# Beacon_schematic.net
KiCad netlist of a schematic drawn in EAGLE
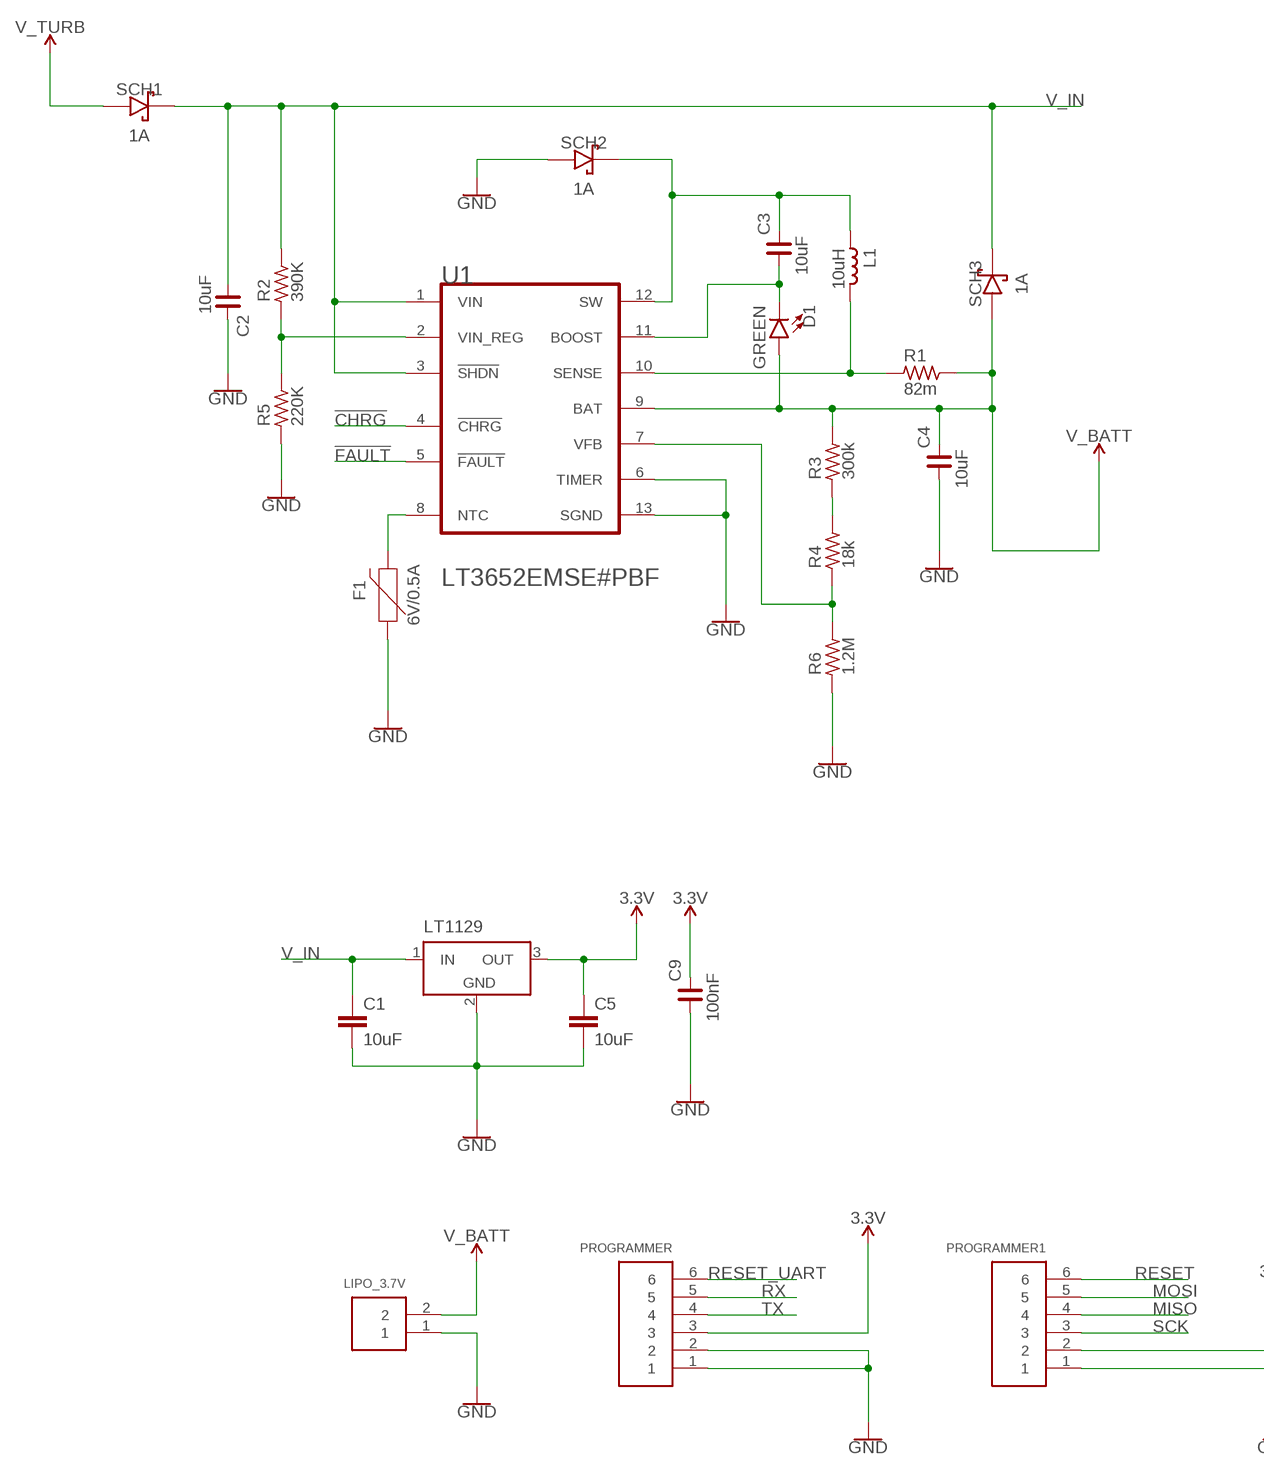
[diagram p0: schematic, sheet 1, part 1 of 2]
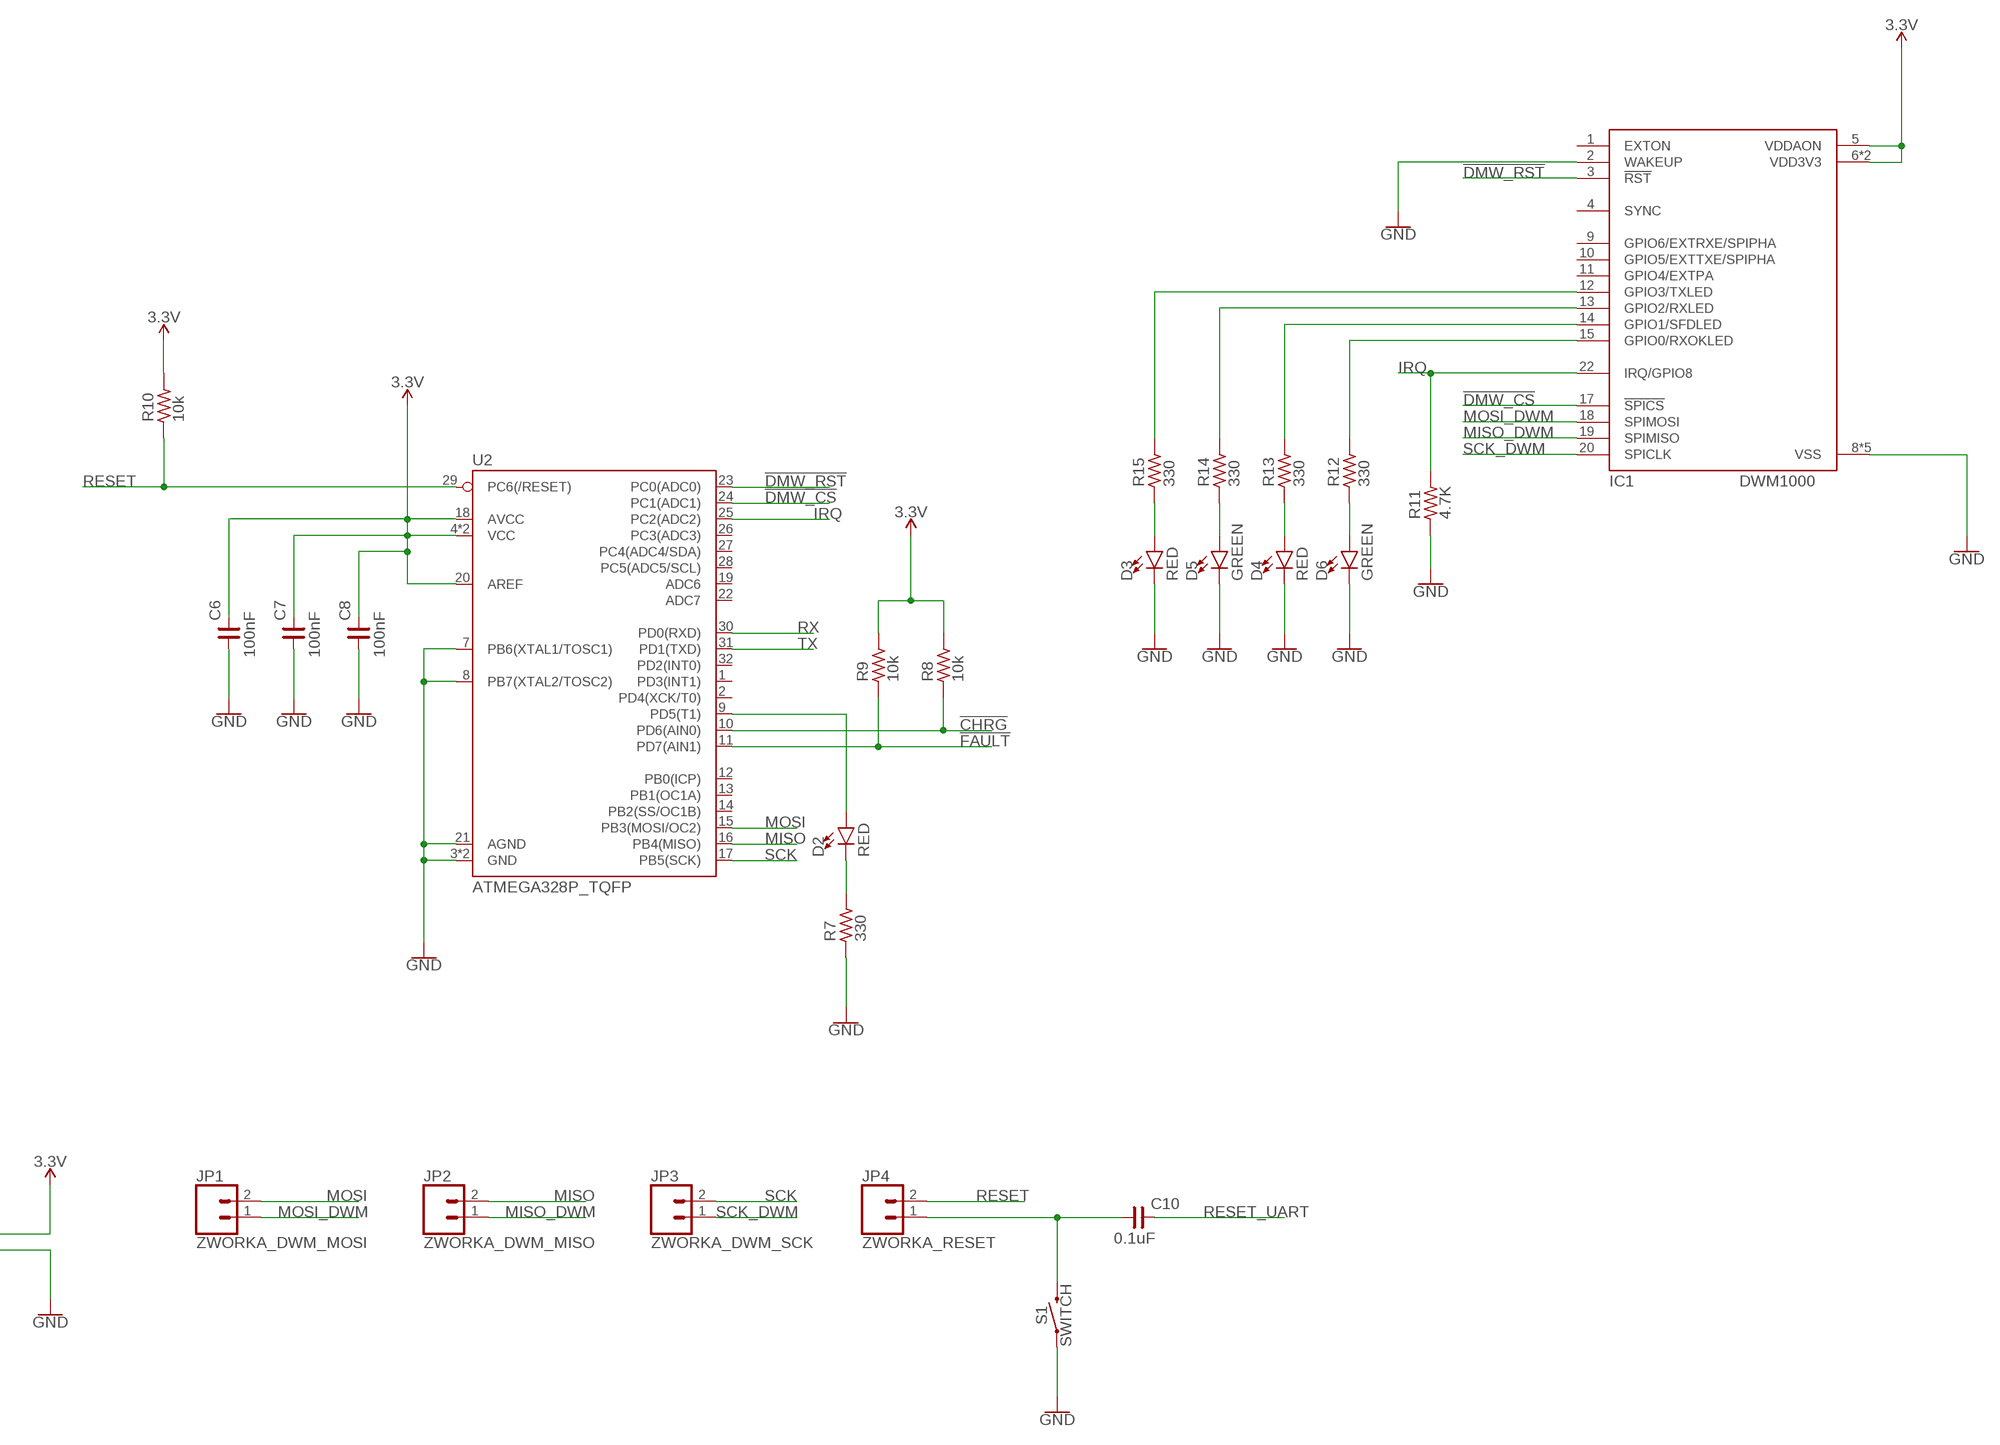
[diagram p1: schematic, sheet 1, part 2 of 2]

(export (version "E")
  (design (tool "Eeschema 10.0.6"))
  (components
    (comp (ref "C1")
      (value "10uF")
      (footprint "eagle-import:1206")
      (libsource (lib "eagle-import") (part "10UF-1206-6.3V-20%"))
    )
    (comp (ref "C2")
      (value "10uF")
      (footprint "eagle-import:C1206")
      (libsource (lib "eagle-import") (part "C_1206"))
    )
    (comp (ref "C3")
      (value "10uF")
      (footprint "eagle-import:C1206")
      (libsource (lib "eagle-import") (part "C_1206"))
    )
    (comp (ref "C4")
      (value "10uF")
      (footprint "eagle-import:C1206")
      (libsource (lib "eagle-import") (part "C_1206"))
    )
    (comp (ref "C5")
      (value "10uF")
      (footprint "eagle-import:1206")
      (libsource (lib "eagle-import") (part "10UF-1206-6.3V-20%"))
    )
    (comp (ref "C6")
      (value "100nF")
      (footprint "eagle-import:C1206")
      (libsource (lib "eagle-import") (part "C_1206"))
    )
    (comp (ref "C7")
      (value "100nF")
      (footprint "eagle-import:C1206")
      (libsource (lib "eagle-import") (part "C_1206"))
    )
    (comp (ref "C8")
      (value "100nF")
      (footprint "eagle-import:C1206")
      (libsource (lib "eagle-import") (part "C_1206"))
    )
    (comp (ref "C9")
      (value "100nF")
      (footprint "eagle-import:C1206")
      (libsource (lib "eagle-import") (part "C_1206"))
    )
    (comp (ref "C10")
      (value "0.1uF")
      (footprint "eagle-import:C1206")
      (libsource (lib "eagle-import") (part "C_1206"))
    )
    (comp (ref "D1")
      (value "GREEN")
      (footprint "eagle-import:LED-1206")
      (libsource (lib "eagle-import") (part "LED-GREEN1206"))
    )
    (comp (ref "D2")
      (value "RED")
      (footprint "eagle-import:LED-1206")
      (libsource (lib "eagle-import") (part "LED-RED1206"))
    )
    (comp (ref "D3")
      (value "RED")
      (footprint "eagle-import:LED-1206")
      (libsource (lib "eagle-import") (part "LED-RED1206"))
    )
    (comp (ref "D4")
      (value "RED")
      (footprint "eagle-import:LED-1206")
      (libsource (lib "eagle-import") (part "LED-RED1206"))
    )
    (comp (ref "D5")
      (value "GREEN")
      (footprint "eagle-import:LED-1206")
      (libsource (lib "eagle-import") (part "LED-GREENLILYPAD"))
    )
    (comp (ref "D6")
      (value "GREEN")
      (footprint "eagle-import:LED-1206")
      (libsource (lib "eagle-import") (part "LED-GREENLILYPAD"))
    )
    (comp (ref "F1")
      (value "6V/0.5A")
      (footprint "eagle-import:1206")
      (libsource (lib "eagle-import") (part "PPTC_HALF-AMP"))
    )
    (comp (ref "IC1")
      (value "DWM1000")
      (footprint "eagle-import:DWM1000")
      (libsource (lib "eagle-import") (part "DWM1000"))
    )
    (comp (ref "JP1")
      (value "ZWORKA_DWM_MOSI")
      (footprint "eagle-import:1X02")
      (libsource (lib "eagle-import") (part "CONN_02"))
    )
    (comp (ref "JP2")
      (value "ZWORKA_DWM_MISO")
      (footprint "eagle-import:1X02")
      (libsource (lib "eagle-import") (part "CONN_02"))
    )
    (comp (ref "JP3")
      (value "ZWORKA_DWM_SCK")
      (footprint "eagle-import:1X02")
      (libsource (lib "eagle-import") (part "CONN_02"))
    )
    (comp (ref "JP4")
      (value "ZWORKA_RESET")
      (footprint "eagle-import:1X02")
      (libsource (lib "eagle-import") (part "CONN_02"))
    )
    (comp (ref "L1")
      (value "10uH")
      (footprint "eagle-import:L1206")
      (libsource (lib "eagle-import") (part "L_1206"))
    )
    (comp (ref "LIPO_3.7V")
      (value "2PIN")
      (footprint "eagle-import:B2B-PH-K-S")
      (libsource (lib "eagle-import") (part "2PIN"))
    )
    (comp (ref "LT1129")
      (value "LT1129CST5")
      (footprint "eagle-import:SOT223")
      (libsource (lib "eagle-import") (part "LT1129CST5"))
    )
    (comp (ref "PROGRAMMER")
      (value "6PIN")
      (footprint "eagle-import:B6B-PH-K-S")
      (libsource (lib "eagle-import") (part "6PIN"))
    )
    (comp (ref "PROGRAMMER1")
      (value "6PIN")
      (footprint "eagle-import:B6B-PH-K-S")
      (libsource (lib "eagle-import") (part "6PIN"))
    )
    (comp (ref "R1")
      (value "82m")
      (footprint "eagle-import:R1206")
      (libsource (lib "eagle-import") (part "R_1206"))
    )
    (comp (ref "R2")
      (value "390K")
      (footprint "eagle-import:R1206")
      (libsource (lib "eagle-import") (part "R_1206"))
    )
    (comp (ref "R3")
      (value "300k")
      (footprint "eagle-import:R1206")
      (libsource (lib "eagle-import") (part "R_1206"))
    )
    (comp (ref "R4")
      (value "18k")
      (footprint "eagle-import:R1206")
      (libsource (lib "eagle-import") (part "R_1206"))
    )
    (comp (ref "R5")
      (value "220K")
      (footprint "eagle-import:R1206")
      (libsource (lib "eagle-import") (part "R_1206"))
    )
    (comp (ref "R6")
      (value "1.2M")
      (footprint "eagle-import:R1206")
      (libsource (lib "eagle-import") (part "R_1206"))
    )
    (comp (ref "R7")
      (value "330")
      (footprint "eagle-import:R1206")
      (libsource (lib "eagle-import") (part "R_1206"))
    )
    (comp (ref "R8")
      (value "10k")
      (footprint "eagle-import:R1206")
      (libsource (lib "eagle-import") (part "R_1206"))
    )
    (comp (ref "R9")
      (value "10k")
      (footprint "eagle-import:R1206")
      (libsource (lib "eagle-import") (part "R_1206"))
    )
    (comp (ref "R10")
      (value "10k")
      (footprint "eagle-import:R1206")
      (libsource (lib "eagle-import") (part "R_1206"))
    )
    (comp (ref "R11")
      (value "4.7K")
      (footprint "eagle-import:R1206")
      (libsource (lib "eagle-import") (part "R_1206"))
    )
    (comp (ref "R12")
      (value "330")
      (footprint "eagle-import:R1206")
      (libsource (lib "eagle-import") (part "R_1206"))
    )
    (comp (ref "R13")
      (value "330")
      (footprint "eagle-import:R1206")
      (libsource (lib "eagle-import") (part "R_1206"))
    )
    (comp (ref "R14")
      (value "330")
      (footprint "eagle-import:R1206")
      (libsource (lib "eagle-import") (part "R_1206"))
    )
    (comp (ref "R15")
      (value "330")
      (footprint "eagle-import:R1206")
      (libsource (lib "eagle-import") (part "R_1206"))
    )
    (comp (ref "S1")
      (value "SWITCH")
      (footprint "eagle-import:TACTILE_SWITCH_SMD_5.2MM")
      (libsource (lib "eagle-import") (part "MOMENTARY-SWITCH-SPST-SMD-5.2-REDUNDANT"))
    )
    (comp (ref "SCH1")
      (value "1A")
      (footprint "eagle-import:SOD123")
      (fields (field (name "MANUFACTURER") "ON Semiconductor") (field (name "MPN") "MBR0520LT1G"))
      (libsource (lib "eagle-import") (part "DIODE_SCHOTTKYMBR0520LT1G"))
    )
    (comp (ref "SCH2")
      (value "1A")
      (footprint "eagle-import:SOD123")
      (fields (field (name "MANUFACTURER") "ON Semiconductor") (field (name "MPN") "MBR0520LT1G"))
      (libsource (lib "eagle-import") (part "DIODE_SCHOTTKYMBR0520LT1G"))
    )
    (comp (ref "SCH3")
      (value "1A")
      (footprint "eagle-import:SOD123")
      (fields (field (name "MANUFACTURER") "ON Semiconductor") (field (name "MPN") "MBR0520LT1G"))
      (libsource (lib "eagle-import") (part "DIODE_SCHOTTKYMBR0520LT1G"))
    )
    (comp (ref "U1")
      (value "LINEAR_TECHNOLOGY_LT3652EMSE#PBFLINEAR_TECHNOLOGY_LT3652EMSE#PBF_0_2")
      (footprint "eagle-import:LINEAR_TECHNOLOGY_LT3652EMSE#PBF_2")
      (fields (field (name "MF") "Linear Technology") (field (name "MPN") "LT3652EMSE#PBF"))
      (libsource (lib "eagle-import") (part "LINEAR_TECHNOLOGY_LT3652EMSE#PBFLINEAR_TECHNOLOGY_LT3652EMSE#PBF_0_2"))
    )
    (comp (ref "U2")
      (value "ATMEGA328P_TQFP")
      (footprint "eagle-import:TQFP32-08")
      (libsource (lib "eagle-import") (part "ATMEGA328P_TQFP"))
    )
  )
  (nets
    (net (code "1") (name "/IRQ") (class "Default")
      (node (ref "IC1") (pin "22") (pinfunction "IRQ/GPIO8_22") (pintype "bidirectional"))
      (node (ref "R11") (pin "2") (pinfunction "2_2") (pintype "passive"))
      (node (ref "U2") (pin "25") (pinfunction "PC2(ADC2)_25") (pintype "bidirectional"))
    )
    (net (code "2") (name "/MISO") (class "Default")
      (node (ref "JP2") (pin "2") (pinfunction "2_2") (pintype "passive"))
      (node (ref "PROGRAMMER1") (pin "4") (pinfunction "4_4") (pintype "bidirectional"))
      (node (ref "U2") (pin "16") (pinfunction "PB4(MISO)_16") (pintype "bidirectional"))
    )
    (net (code "3") (name "/MISO_DWM") (class "Default")
      (node (ref "IC1") (pin "19") (pinfunction "SPIMISO_19") (pintype "bidirectional"))
      (node (ref "JP2") (pin "1") (pinfunction "1_1") (pintype "passive"))
    )
    (net (code "4") (name "/MOSI") (class "Default")
      (node (ref "JP1") (pin "2") (pinfunction "2_2") (pintype "passive"))
      (node (ref "PROGRAMMER1") (pin "5") (pinfunction "5_5") (pintype "bidirectional"))
      (node (ref "U2") (pin "15") (pinfunction "PB3(MOSI/OC2)_15") (pintype "bidirectional"))
    )
    (net (code "5") (name "/MOSI_DWM") (class "Default")
      (node (ref "IC1") (pin "18") (pinfunction "SPIMOSI_18") (pintype "bidirectional"))
      (node (ref "JP1") (pin "1") (pinfunction "1_1") (pintype "passive"))
    )
    (net (code "6") (name "/RESET") (class "Default")
      (node (ref "JP4") (pin "2") (pinfunction "2_2") (pintype "passive"))
      (node (ref "PROGRAMMER1") (pin "6") (pinfunction "6_6") (pintype "bidirectional"))
      (node (ref "R10") (pin "1") (pinfunction "1_1") (pintype "passive"))
      (node (ref "U2") (pin "29") (pinfunction "PC6(/RESET)_29") (pintype "bidirectional"))
    )
    (net (code "7") (name "/RESET_UART") (class "Default")
      (node (ref "C10") (pin "2") (pinfunction "2_2") (pintype "passive"))
      (node (ref "PROGRAMMER") (pin "6") (pinfunction "6_6") (pintype "bidirectional"))
    )
    (net (code "8") (name "/RX") (class "Default")
      (node (ref "PROGRAMMER") (pin "5") (pinfunction "5_5") (pintype "bidirectional"))
      (node (ref "U2") (pin "30") (pinfunction "PD0(RXD)_30") (pintype "bidirectional"))
    )
    (net (code "9") (name "/SCK") (class "Default")
      (node (ref "JP3") (pin "2") (pinfunction "2_2") (pintype "passive"))
      (node (ref "PROGRAMMER1") (pin "3") (pinfunction "3_3") (pintype "bidirectional"))
      (node (ref "U2") (pin "17") (pinfunction "PB5(SCK)_17") (pintype "bidirectional"))
    )
    (net (code "10") (name "/SCK_DWM") (class "Default")
      (node (ref "IC1") (pin "20") (pinfunction "SPICLK_20") (pintype "bidirectional"))
      (node (ref "JP3") (pin "1") (pinfunction "1_1") (pintype "passive"))
    )
    (net (code "11") (name "/TX") (class "Default")
      (node (ref "PROGRAMMER") (pin "4") (pinfunction "4_4") (pintype "bidirectional"))
      (node (ref "U2") (pin "31") (pinfunction "PD1(TXD)_31") (pintype "bidirectional"))
    )
    (net (code "12") (name "/V_IN") (class "Default")
      (node (ref "C1") (pin "1") (pinfunction "1_1") (pintype "passive"))
      (node (ref "C2") (pin "1") (pinfunction "1_1") (pintype "passive"))
      (node (ref "LT1129") (pin "1") (pinfunction "IN_1") (pintype "input"))
      (node (ref "R2") (pin "2") (pinfunction "2_2") (pintype "passive"))
      (node (ref "SCH1") (pin "K") (pinfunction "CATHODE_K") (pintype "bidirectional"))
      (node (ref "SCH3") (pin "K") (pinfunction "CATHODE_K") (pintype "bidirectional"))
      (node (ref "U1") (pin "1") (pinfunction "VIN_1") (pintype "power_in"))
      (node (ref "U1") (pin "3") (pinfunction "~{SHDN}_3") (pintype "input"))
    )
    (net (code "13") (name "/~{CHRG}") (class "Default")
      (node (ref "R8") (pin "1") (pinfunction "1_1") (pintype "passive"))
      (node (ref "U1") (pin "4") (pinfunction "~{CHRG}_4") (pintype "tri_state"))
      (node (ref "U2") (pin "10") (pinfunction "PD6(AIN0)_10") (pintype "bidirectional"))
    )
    (net (code "14") (name "/~{DMW_CS}") (class "Default")
      (node (ref "IC1") (pin "17") (pinfunction "~{SPICS}_17") (pintype "bidirectional"))
      (node (ref "U2") (pin "24") (pinfunction "PC1(ADC1)_24") (pintype "bidirectional"))
    )
    (net (code "15") (name "/~{DMW_RST}") (class "Default")
      (node (ref "IC1") (pin "3") (pinfunction "~{RST}_3") (pintype "bidirectional"))
      (node (ref "U2") (pin "23") (pinfunction "PC0(ADC0)_23") (pintype "bidirectional"))
    )
    (net (code "16") (name "/~{FAULT}") (class "Default")
      (node (ref "R9") (pin "1") (pinfunction "1_1") (pintype "passive"))
      (node (ref "U1") (pin "5") (pinfunction "~{FAULT}_5") (pintype "tri_state"))
      (node (ref "U2") (pin "11") (pinfunction "PD7(AIN1)_11") (pintype "bidirectional"))
    )
    (net (code "17") (name "3.3V") (class "Default")
      (node (ref "C5") (pin "1") (pinfunction "1_1") (pintype "passive"))
      (node (ref "C6") (pin "2") (pinfunction "2_2") (pintype "passive"))
      (node (ref "C7") (pin "2") (pinfunction "2_2") (pintype "passive"))
      (node (ref "C8") (pin "2") (pinfunction "2_2") (pintype "passive"))
      (node (ref "C9") (pin "2") (pinfunction "2_2") (pintype "passive"))
      (node (ref "IC1") (pin "5") (pinfunction "VDDAON_5") (pintype "bidirectional"))
      (node (ref "IC1") (pin "6") (pinfunction "VDD3V3_6") (pintype "bidirectional"))
      (node (ref "IC1") (pin "7") (pinfunction "VDD3V3_7") (pintype "bidirectional"))
      (node (ref "LT1129") (pin "3") (pinfunction "OUT_3") (pintype "output"))
      (node (ref "PROGRAMMER") (pin "3") (pinfunction "3_3") (pintype "bidirectional"))
      (node (ref "PROGRAMMER1") (pin "2") (pinfunction "2_2") (pintype "bidirectional"))
      (node (ref "R10") (pin "2") (pinfunction "2_2") (pintype "passive"))
      (node (ref "R8") (pin "2") (pinfunction "2_2") (pintype "passive"))
      (node (ref "R9") (pin "2") (pinfunction "2_2") (pintype "passive"))
      (node (ref "U2") (pin "18") (pinfunction "AVCC_18") (pintype "bidirectional"))
      (node (ref "U2") (pin "20") (pinfunction "AREF_20") (pintype "bidirectional"))
      (node (ref "U2") (pin "4") (pinfunction "VCC_4") (pintype "bidirectional"))
      (node (ref "U2") (pin "6") (pinfunction "VCC_6") (pintype "bidirectional"))
    )
    (net (code "18") (name "GND") (class "Default")
      (node (ref "C1") (pin "2") (pinfunction "2_2") (pintype "passive"))
      (node (ref "C2") (pin "2") (pinfunction "2_2") (pintype "passive"))
      (node (ref "C4") (pin "1") (pinfunction "1_1") (pintype "passive"))
      (node (ref "C5") (pin "2") (pinfunction "2_2") (pintype "passive"))
      (node (ref "C6") (pin "1") (pinfunction "1_1") (pintype "passive"))
      (node (ref "C7") (pin "1") (pinfunction "1_1") (pintype "passive"))
      (node (ref "C8") (pin "1") (pinfunction "1_1") (pintype "passive"))
      (node (ref "C9") (pin "1") (pinfunction "1_1") (pintype "passive"))
      (node (ref "D3") (pin "C") (pinfunction "C_C") (pintype "passive"))
      (node (ref "D4") (pin "C") (pinfunction "C_C") (pintype "passive"))
      (node (ref "D5") (pin "C") (pinfunction "C_C") (pintype "passive"))
      (node (ref "D6") (pin "C") (pinfunction "C_C") (pintype "passive"))
      (node (ref "F1") (pin "1") (pinfunction "1_1") (pintype "bidirectional"))
      (node (ref "IC1") (pin "16") (pinfunction "VSS_16") (pintype "bidirectional"))
      (node (ref "IC1") (pin "2") (pinfunction "WAKEUP_2") (pintype "bidirectional"))
      (node (ref "IC1") (pin "21") (pinfunction "VSS_21") (pintype "bidirectional"))
      (node (ref "IC1") (pin "23") (pinfunction "VSS_23") (pintype "bidirectional"))
      (node (ref "IC1") (pin "24") (pinfunction "VSS_24") (pintype "bidirectional"))
      (node (ref "IC1") (pin "8") (pinfunction "VSS_8") (pintype "bidirectional"))
      (node (ref "LIPO_3.7V") (pin "1") (pinfunction "1_1") (pintype "bidirectional"))
      (node (ref "LT1129") (pin "2") (pinfunction "GND_2") (pintype "power_in"))
      (node (ref "PROGRAMMER") (pin "1") (pinfunction "1_1") (pintype "bidirectional"))
      (node (ref "PROGRAMMER") (pin "2") (pinfunction "2_2") (pintype "bidirectional"))
      (node (ref "PROGRAMMER1") (pin "1") (pinfunction "1_1") (pintype "bidirectional"))
      (node (ref "R11") (pin "1") (pinfunction "1_1") (pintype "passive"))
      (node (ref "R5") (pin "1") (pinfunction "1_1") (pintype "passive"))
      (node (ref "R6") (pin "1") (pinfunction "1_1") (pintype "passive"))
      (node (ref "R7") (pin "1") (pinfunction "1_1") (pintype "passive"))
      (node (ref "S1") (pin "1") (pinfunction "1_1") (pintype "passive"))
      (node (ref "S1") (pin "2") (pinfunction "1_2") (pintype "passive"))
      (node (ref "SCH2") (pin "A") (pinfunction "ANODE_A") (pintype "bidirectional"))
      (node (ref "U1") (pin "13") (pinfunction "SGND_13") (pintype "power_in"))
      (node (ref "U1") (pin "6") (pinfunction "TIMER_6") (pintype "input"))
      (node (ref "U2") (pin "21") (pinfunction "AGND_21") (pintype "bidirectional"))
      (node (ref "U2") (pin "3") (pinfunction "GND_3") (pintype "bidirectional"))
      (node (ref "U2") (pin "5") (pinfunction "GND_5") (pintype "bidirectional"))
      (node (ref "U2") (pin "7") (pinfunction "PB6(XTAL1/TOSC1)_7") (pintype "bidirectional"))
      (node (ref "U2") (pin "8") (pinfunction "PB7(XTAL2/TOSC2)_8") (pintype "bidirectional"))
    )
    (net (code "19") (name "Net-(C10-Pad1)") (class "Default")
      (node (ref "C10") (pin "1") (pinfunction "1_1") (pintype "passive"))
      (node (ref "JP4") (pin "1") (pinfunction "1_1") (pintype "passive"))
      (node (ref "S1") (pin "3") (pinfunction "2_3") (pintype "passive"))
      (node (ref "S1") (pin "4") (pinfunction "2_4") (pintype "passive"))
    )
    (net (code "20") (name "Net-(D2-PadC)") (class "Default")
      (node (ref "D2") (pin "C") (pinfunction "C_C") (pintype "passive"))
      (node (ref "R7") (pin "2") (pinfunction "2_2") (pintype "passive"))
    )
    (net (code "21") (name "Net-(D3-PadA)") (class "Default")
      (node (ref "D3") (pin "A") (pinfunction "A_A") (pintype "passive"))
      (node (ref "R15") (pin "1") (pinfunction "1_1") (pintype "passive"))
    )
    (net (code "22") (name "Net-(D4-PadA)") (class "Default")
      (node (ref "D4") (pin "A") (pinfunction "A_A") (pintype "passive"))
      (node (ref "R13") (pin "1") (pinfunction "1_1") (pintype "passive"))
    )
    (net (code "23") (name "Net-(D5-PadA)") (class "Default")
      (node (ref "D5") (pin "A") (pinfunction "A_A") (pintype "passive"))
      (node (ref "R14") (pin "1") (pinfunction "1_1") (pintype "passive"))
    )
    (net (code "24") (name "Net-(D6-PadA)") (class "Default")
      (node (ref "D6") (pin "A") (pinfunction "A_A") (pintype "passive"))
      (node (ref "R12") (pin "1") (pinfunction "1_1") (pintype "passive"))
    )
    (net (code "25") (name "Net-(IC1-GPIO0{slash}RXOKLED)") (class "Default")
      (node (ref "IC1") (pin "15") (pinfunction "GPIO0/RXOKLED_15") (pintype "bidirectional"))
      (node (ref "R12") (pin "2") (pinfunction "2_2") (pintype "passive"))
    )
    (net (code "26") (name "Net-(IC1-GPIO1{slash}SFDLED)") (class "Default")
      (node (ref "IC1") (pin "14") (pinfunction "GPIO1/SFDLED_14") (pintype "bidirectional"))
      (node (ref "R13") (pin "2") (pinfunction "2_2") (pintype "passive"))
    )
    (net (code "27") (name "Net-(IC1-GPIO2{slash}RXLED)") (class "Default")
      (node (ref "IC1") (pin "13") (pinfunction "GPIO2/RXLED_13") (pintype "bidirectional"))
      (node (ref "R14") (pin "2") (pinfunction "2_2") (pintype "passive"))
    )
    (net (code "28") (name "Net-(IC1-GPIO3{slash}TXLED)") (class "Default")
      (node (ref "IC1") (pin "12") (pinfunction "GPIO3/TXLED_12") (pintype "bidirectional"))
      (node (ref "R15") (pin "2") (pinfunction "2_2") (pintype "passive"))
    )
    (net (code "29") (name "Net-(R3-Pad1)") (class "Default")
      (node (ref "R3") (pin "1") (pinfunction "1_1") (pintype "passive"))
      (node (ref "R4") (pin "2") (pinfunction "2_2") (pintype "passive"))
    )
    (net (code "30") (name "Net-(SCH2-CATHODE)") (class "Default")
      (node (ref "C3") (pin "2") (pinfunction "2_2") (pintype "passive"))
      (node (ref "L1") (pin "2") (pinfunction "2_2") (pintype "passive"))
      (node (ref "SCH2") (pin "K") (pinfunction "CATHODE_K") (pintype "bidirectional"))
      (node (ref "U1") (pin "12") (pinfunction "SW_12") (pintype "power_in"))
    )
    (net (code "31") (name "Net-(U1-BOOST)") (class "Default")
      (node (ref "C3") (pin "1") (pinfunction "1_1") (pintype "passive"))
      (node (ref "D1") (pin "C") (pinfunction "C_C") (pintype "passive"))
      (node (ref "U1") (pin "11") (pinfunction "BOOST_11") (pintype "power_in"))
    )
    (net (code "32") (name "Net-(U1-NTC)") (class "Default")
      (node (ref "F1") (pin "2") (pinfunction "2_2") (pintype "bidirectional"))
      (node (ref "U1") (pin "8") (pinfunction "NTC_8") (pintype "input"))
    )
    (net (code "33") (name "Net-(U1-SENSE)") (class "Default")
      (node (ref "L1") (pin "1") (pinfunction "1_1") (pintype "passive"))
      (node (ref "R1") (pin "1") (pinfunction "1_1") (pintype "passive"))
      (node (ref "U1") (pin "10") (pinfunction "SENSE_10") (pintype "input"))
    )
    (net (code "34") (name "Net-(U1-VFB)") (class "Default")
      (node (ref "R4") (pin "1") (pinfunction "1_1") (pintype "passive"))
      (node (ref "R6") (pin "2") (pinfunction "2_2") (pintype "passive"))
      (node (ref "U1") (pin "7") (pinfunction "VFB_7") (pintype "input"))
    )
    (net (code "35") (name "Net-(U1-VIN_REG)") (class "Default")
      (node (ref "R2") (pin "1") (pinfunction "1_1") (pintype "passive"))
      (node (ref "R5") (pin "2") (pinfunction "2_2") (pintype "passive"))
      (node (ref "U1") (pin "2") (pinfunction "VIN_REG_2") (pintype "input"))
    )
    (net (code "36") (name "Net-(U2-PD5(T1))") (class "Default")
      (node (ref "D2") (pin "A") (pinfunction "A_A") (pintype "passive"))
      (node (ref "U2") (pin "9") (pinfunction "PD5(T1)_9") (pintype "bidirectional"))
    )
    (net (code "37") (name "V_BATT") (class "Default")
      (node (ref "C4") (pin "2") (pinfunction "2_2") (pintype "passive"))
      (node (ref "D1") (pin "A") (pinfunction "A_A") (pintype "passive"))
      (node (ref "LIPO_3.7V") (pin "2") (pinfunction "2_2") (pintype "bidirectional"))
      (node (ref "R1") (pin "2") (pinfunction "2_2") (pintype "passive"))
      (node (ref "R3") (pin "2") (pinfunction "2_2") (pintype "passive"))
      (node (ref "SCH1") (pin "A") (pinfunction "ANODE_A") (pintype "bidirectional"))
      (node (ref "SCH3") (pin "A") (pinfunction "ANODE_A") (pintype "bidirectional"))
      (node (ref "U1") (pin "9") (pinfunction "BAT_9") (pintype "input"))
    )
    (net (code "38") (name "unconnected-(IC1-EXTON-Pad1)") (class "Default")
      (node (ref "IC1") (pin "1") (pinfunction "EXTON_1") (pintype "bidirectional"))
    )
    (net (code "39") (name "unconnected-(IC1-GPIO4{slash}EXTPA-Pad11)") (class "Default")
      (node (ref "IC1") (pin "11") (pinfunction "GPIO4/EXTPA_11") (pintype "bidirectional"))
    )
    (net (code "40") (name "unconnected-(IC1-GPIO5{slash}EXTTXE{slash}SPIPHA-Pad10)") (class "Default")
      (node (ref "IC1") (pin "10") (pinfunction "GPIO5/EXTTXE/SPIPHA_10") (pintype "bidirectional"))
    )
    (net (code "41") (name "unconnected-(IC1-GPIO6{slash}EXTRXE{slash}SPIPHA-Pad9)") (class "Default")
      (node (ref "IC1") (pin "9") (pinfunction "GPIO6/EXTRXE/SPIPHA_9") (pintype "bidirectional"))
    )
    (net (code "42") (name "unconnected-(IC1-SYNC-Pad4)") (class "Default")
      (node (ref "IC1") (pin "4") (pinfunction "SYNC_4") (pintype "bidirectional"))
    )
    (net (code "43") (name "unconnected-(U2-ADC6-Pad19)") (class "Default")
      (node (ref "U2") (pin "19") (pinfunction "ADC6_19") (pintype "bidirectional"))
    )
    (net (code "44") (name "unconnected-(U2-ADC7-Pad22)") (class "Default")
      (node (ref "U2") (pin "22") (pinfunction "ADC7_22") (pintype "bidirectional"))
    )
    (net (code "45") (name "unconnected-(U2-PB0(ICP)-Pad12)") (class "Default")
      (node (ref "U2") (pin "12") (pinfunction "PB0(ICP)_12") (pintype "bidirectional"))
    )
    (net (code "46") (name "unconnected-(U2-PB1(OC1A)-Pad13)") (class "Default")
      (node (ref "U2") (pin "13") (pinfunction "PB1(OC1A)_13") (pintype "bidirectional"))
    )
    (net (code "47") (name "unconnected-(U2-PB2(SS{slash}OC1B)-Pad14)") (class "Default")
      (node (ref "U2") (pin "14") (pinfunction "PB2(SS/OC1B)_14") (pintype "bidirectional"))
    )
    (net (code "48") (name "unconnected-(U2-PC3(ADC3)-Pad26)") (class "Default")
      (node (ref "U2") (pin "26") (pinfunction "PC3(ADC3)_26") (pintype "bidirectional"))
    )
    (net (code "49") (name "unconnected-(U2-PC4(ADC4{slash}SDA)-Pad27)") (class "Default")
      (node (ref "U2") (pin "27") (pinfunction "PC4(ADC4/SDA)_27") (pintype "bidirectional"))
    )
    (net (code "50") (name "unconnected-(U2-PC5(ADC5{slash}SCL)-Pad28)") (class "Default")
      (node (ref "U2") (pin "28") (pinfunction "PC5(ADC5/SCL)_28") (pintype "bidirectional"))
    )
    (net (code "51") (name "unconnected-(U2-PD2(INT0)-Pad32)") (class "Default")
      (node (ref "U2") (pin "32") (pinfunction "PD2(INT0)_32") (pintype "bidirectional"))
    )
    (net (code "52") (name "unconnected-(U2-PD3(INT1)-Pad1)") (class "Default")
      (node (ref "U2") (pin "1") (pinfunction "PD3(INT1)_1") (pintype "bidirectional"))
    )
    (net (code "53") (name "unconnected-(U2-PD4(XCK{slash}T0)-Pad2)") (class "Default")
      (node (ref "U2") (pin "2") (pinfunction "PD4(XCK/T0)_2") (pintype "bidirectional"))
    )
  )
)
